# project_2_schematic.net
KiCad netlist of a schematic drawn in EAGLE
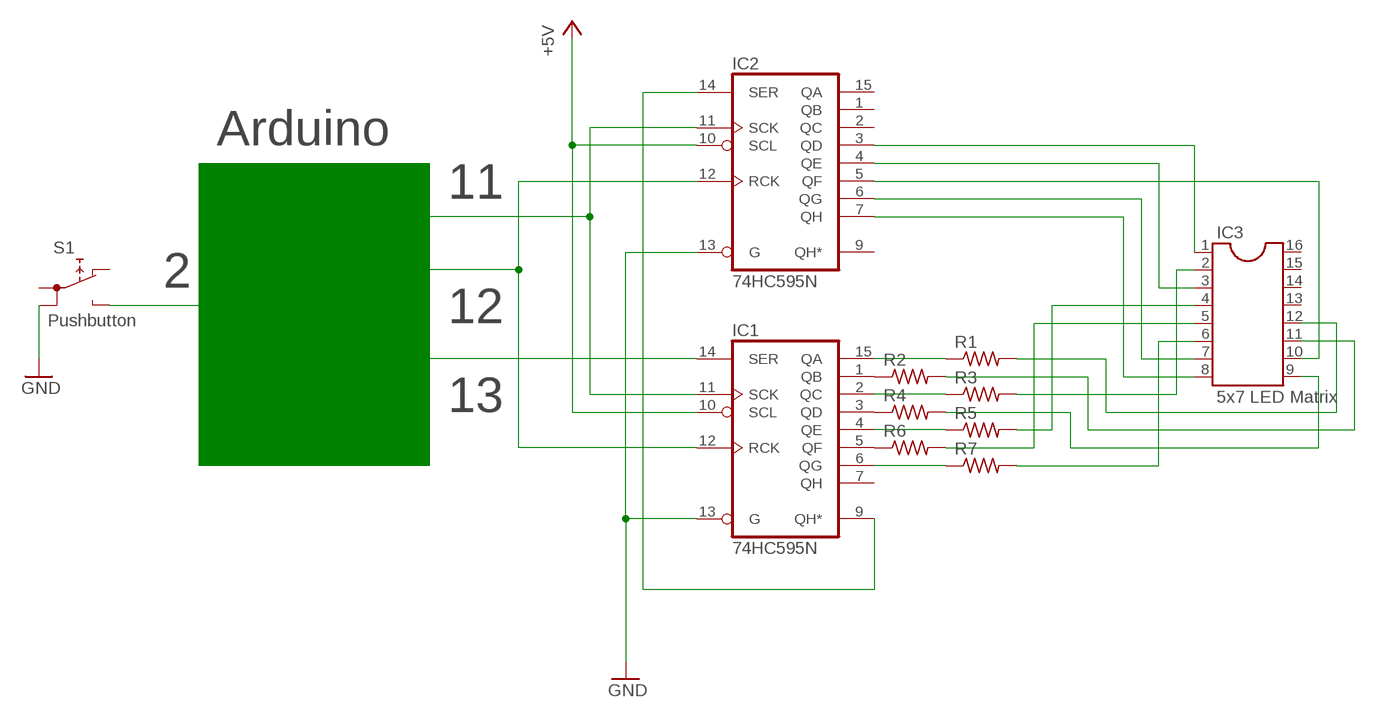
[diagram p0: schematic, sheet 1]

(export (version "E")
  (design (tool "Eeschema 10.0.6"))
  (components
    (comp (ref "IC1")
      (value "74HC595N")
      (footprint "eagle-import:DIL16")
      (libsource (lib "eagle-import") (part "74595NHC"))
    )
    (comp (ref "IC2")
      (value "74HC595N")
      (footprint "eagle-import:DIL16")
      (libsource (lib "eagle-import") (part "74595NHC"))
    )
    (comp (ref "IC3")
      (value "5x7 LED Matrix")
      (footprint "eagle-import:DIL16")
      (libsource (lib "eagle-import") (part "DIL16"))
    )
    (comp (ref "R1")
      (value "R-US_0207/10")
      (footprint "eagle-import:0207_10")
      (libsource (lib "eagle-import") (part "R-US_0207/10"))
    )
    (comp (ref "R2")
      (value "R-US_0207/10")
      (footprint "eagle-import:0207_10")
      (libsource (lib "eagle-import") (part "R-US_0207/10"))
    )
    (comp (ref "R3")
      (value "R-US_0207/10")
      (footprint "eagle-import:0207_10")
      (libsource (lib "eagle-import") (part "R-US_0207/10"))
    )
    (comp (ref "R4")
      (value "R-US_0207/10")
      (footprint "eagle-import:0207_10")
      (libsource (lib "eagle-import") (part "R-US_0207/10"))
    )
    (comp (ref "R5")
      (value "R-US_0207/10")
      (footprint "eagle-import:0207_10")
      (libsource (lib "eagle-import") (part "R-US_0207/10"))
    )
    (comp (ref "R6")
      (value "R-US_0207/10")
      (footprint "eagle-import:0207_10")
      (libsource (lib "eagle-import") (part "R-US_0207/10"))
    )
    (comp (ref "R7")
      (value "R-US_0207/10")
      (footprint "eagle-import:0207_10")
      (libsource (lib "eagle-import") (part "R-US_0207/10"))
    )
    (comp (ref "S1")
      (value "Pushbutton")
      (footprint "eagle-import:5501")
      (libsource (lib "eagle-import") (part "55?01"))
    )
  )
  (nets
    (net (code "1") (name "+5V") (class "Default")
      (node (ref "IC1") (pin "10") (pinfunction "SCL_10") (pintype "input"))
      (node (ref "IC2") (pin "10") (pinfunction "SCL_10") (pintype "input"))
    )
    (net (code "2") (name "GND") (class "Default")
      (node (ref "IC1") (pin "13") (pinfunction "G_13") (pintype "input"))
      (node (ref "IC2") (pin "13") (pinfunction "G_13") (pintype "input"))
      (node (ref "S1") (pin "1B") (pinfunction "1B_1B") (pintype "passive"))
    )
    (net (code "3") (name "Net-(IC1A-QA)") (class "Default")
      (node (ref "IC1") (pin "15") (pinfunction "QA_15") (pintype "tri_state"))
      (node (ref "R1") (pin "1") (pinfunction "1_1") (pintype "passive"))
    )
    (net (code "4") (name "Net-(IC1A-QB)") (class "Default")
      (node (ref "IC1") (pin "1") (pinfunction "QB_1") (pintype "tri_state"))
      (node (ref "R2") (pin "1") (pinfunction "1_1") (pintype "passive"))
    )
    (net (code "5") (name "Net-(IC1A-QC)") (class "Default")
      (node (ref "IC1") (pin "2") (pinfunction "QC_2") (pintype "tri_state"))
      (node (ref "R3") (pin "1") (pinfunction "1_1") (pintype "passive"))
    )
    (net (code "6") (name "Net-(IC1A-QD)") (class "Default")
      (node (ref "IC1") (pin "3") (pinfunction "QD_3") (pintype "tri_state"))
      (node (ref "R4") (pin "1") (pinfunction "1_1") (pintype "passive"))
    )
    (net (code "7") (name "Net-(IC1A-QE)") (class "Default")
      (node (ref "IC1") (pin "4") (pinfunction "QE_4") (pintype "tri_state"))
      (node (ref "R5") (pin "1") (pinfunction "1_1") (pintype "passive"))
    )
    (net (code "8") (name "Net-(IC1A-QF)") (class "Default")
      (node (ref "IC1") (pin "5") (pinfunction "QF_5") (pintype "tri_state"))
      (node (ref "R6") (pin "1") (pinfunction "1_1") (pintype "passive"))
    )
    (net (code "9") (name "Net-(IC1A-QG)") (class "Default")
      (node (ref "IC1") (pin "6") (pinfunction "QG_6") (pintype "tri_state"))
      (node (ref "R7") (pin "1") (pinfunction "1_1") (pintype "passive"))
    )
    (net (code "10") (name "Net-(IC1A-QH*)") (class "Default")
      (node (ref "IC1") (pin "9") (pinfunction "QH*_9") (pintype "tri_state"))
      (node (ref "IC2") (pin "14") (pinfunction "SER_14") (pintype "input"))
    )
    (net (code "11") (name "Net-(IC1A-RCK)") (class "Default")
      (node (ref "IC1") (pin "12") (pinfunction "RCK_12") (pintype "input"))
      (node (ref "IC2") (pin "12") (pinfunction "RCK_12") (pintype "input"))
    )
    (net (code "12") (name "Net-(IC1A-SCK)") (class "Default")
      (node (ref "IC1") (pin "11") (pinfunction "SCK_11") (pintype "input"))
      (node (ref "IC2") (pin "11") (pinfunction "SCK_11") (pintype "input"))
    )
    (net (code "13") (name "Net-(IC2A-QD)") (class "Default")
      (node (ref "IC2") (pin "3") (pinfunction "QD_3") (pintype "tri_state"))
      (node (ref "IC3") (pin "1") (pinfunction "1_1") (pintype "passive"))
    )
    (net (code "14") (name "Net-(IC2A-QE)") (class "Default")
      (node (ref "IC2") (pin "4") (pinfunction "QE_4") (pintype "tri_state"))
      (node (ref "IC3") (pin "3") (pinfunction "3_3") (pintype "passive"))
    )
    (net (code "15") (name "Net-(IC2A-QF)") (class "Default")
      (node (ref "IC2") (pin "5") (pinfunction "QF_5") (pintype "tri_state"))
      (node (ref "IC3") (pin "10") (pinfunction "10_10") (pintype "passive"))
    )
    (net (code "16") (name "Net-(IC2A-QG)") (class "Default")
      (node (ref "IC2") (pin "6") (pinfunction "QG_6") (pintype "tri_state"))
      (node (ref "IC3") (pin "7") (pinfunction "7_7") (pintype "passive"))
    )
    (net (code "17") (name "Net-(IC2A-QH)") (class "Default")
      (node (ref "IC2") (pin "7") (pinfunction "QH_7") (pintype "tri_state"))
      (node (ref "IC3") (pin "8") (pinfunction "8_8") (pintype "passive"))
    )
    (net (code "18") (name "Net-(IC3-Pad2)") (class "Default")
      (node (ref "IC3") (pin "2") (pinfunction "2_2") (pintype "passive"))
      (node (ref "R3") (pin "2") (pinfunction "2_2") (pintype "passive"))
    )
    (net (code "19") (name "Net-(IC3-Pad4)") (class "Default")
      (node (ref "IC3") (pin "4") (pinfunction "4_4") (pintype "passive"))
      (node (ref "R5") (pin "2") (pinfunction "2_2") (pintype "passive"))
    )
    (net (code "20") (name "Net-(IC3-Pad5)") (class "Default")
      (node (ref "IC3") (pin "5") (pinfunction "5_5") (pintype "passive"))
      (node (ref "R6") (pin "2") (pinfunction "2_2") (pintype "passive"))
    )
    (net (code "21") (name "Net-(IC3-Pad6)") (class "Default")
      (node (ref "IC3") (pin "6") (pinfunction "6_6") (pintype "passive"))
      (node (ref "R7") (pin "2") (pinfunction "2_2") (pintype "passive"))
    )
    (net (code "22") (name "Net-(IC3-Pad9)") (class "Default")
      (node (ref "IC3") (pin "9") (pinfunction "9_9") (pintype "passive"))
      (node (ref "R4") (pin "2") (pinfunction "2_2") (pintype "passive"))
    )
    (net (code "23") (name "Net-(IC3-Pad11)") (class "Default")
      (node (ref "IC3") (pin "11") (pinfunction "11_11") (pintype "passive"))
      (node (ref "R2") (pin "2") (pinfunction "2_2") (pintype "passive"))
    )
    (net (code "24") (name "Net-(IC3-Pad12)") (class "Default")
      (node (ref "IC3") (pin "12") (pinfunction "12_12") (pintype "passive"))
      (node (ref "R1") (pin "2") (pinfunction "2_2") (pintype "passive"))
    )
    (net (code "25") (name "unconnected-(IC1A-QH-Pad7)") (class "Default")
      (node (ref "IC1") (pin "7") (pinfunction "QH_7") (pintype "tri_state"))
    )
    (net (code "26") (name "unconnected-(IC1A-SER-Pad14)") (class "Default")
      (node (ref "IC1") (pin "14") (pinfunction "SER_14") (pintype "input"))
    )
    (net (code "27") (name "unconnected-(IC2A-QA-Pad15)") (class "Default")
      (node (ref "IC2") (pin "15") (pinfunction "QA_15") (pintype "tri_state"))
    )
    (net (code "28") (name "unconnected-(IC2A-QB-Pad1)") (class "Default")
      (node (ref "IC2") (pin "1") (pinfunction "QB_1") (pintype "tri_state"))
    )
    (net (code "29") (name "unconnected-(IC2A-QC-Pad2)") (class "Default")
      (node (ref "IC2") (pin "2") (pinfunction "QC_2") (pintype "tri_state"))
    )
    (net (code "30") (name "unconnected-(IC2A-QH*-Pad9)") (class "Default")
      (node (ref "IC2") (pin "9") (pinfunction "QH*_9") (pintype "tri_state"))
    )
    (net (code "31") (name "unconnected-(IC3-Pad13)") (class "Default")
      (node (ref "IC3") (pin "13") (pinfunction "13_13") (pintype "passive"))
    )
    (net (code "32") (name "unconnected-(IC3-Pad14)") (class "Default")
      (node (ref "IC3") (pin "14") (pinfunction "14_14") (pintype "passive"))
    )
    (net (code "33") (name "unconnected-(IC3-Pad15)") (class "Default")
      (node (ref "IC3") (pin "15") (pinfunction "15_15") (pintype "passive"))
    )
    (net (code "34") (name "unconnected-(IC3-Pad16)") (class "Default")
      (node (ref "IC3") (pin "16") (pinfunction "16_16") (pintype "passive"))
    )
    (net (code "35") (name "unconnected-(S1-Pad1A)") (class "Default")
      (node (ref "S1") (pin "1A") (pinfunction "1A_1A") (pintype "passive"))
    )
    (net (code "36") (name "unconnected-(S1-PadNC)") (class "Default")
      (node (ref "S1") (pin "NC") (pinfunction "NC_NC") (pintype "passive"))
    )
    (net (code "37") (name "unconnected-(S1-PadNO)") (class "Default")
      (node (ref "S1") (pin "NO") (pinfunction "NO_NO") (pintype "passive"))
    )
  )
)
